# Differenzverst_rker_neu.net
KiCad netlist of a schematic drawn in EAGLE
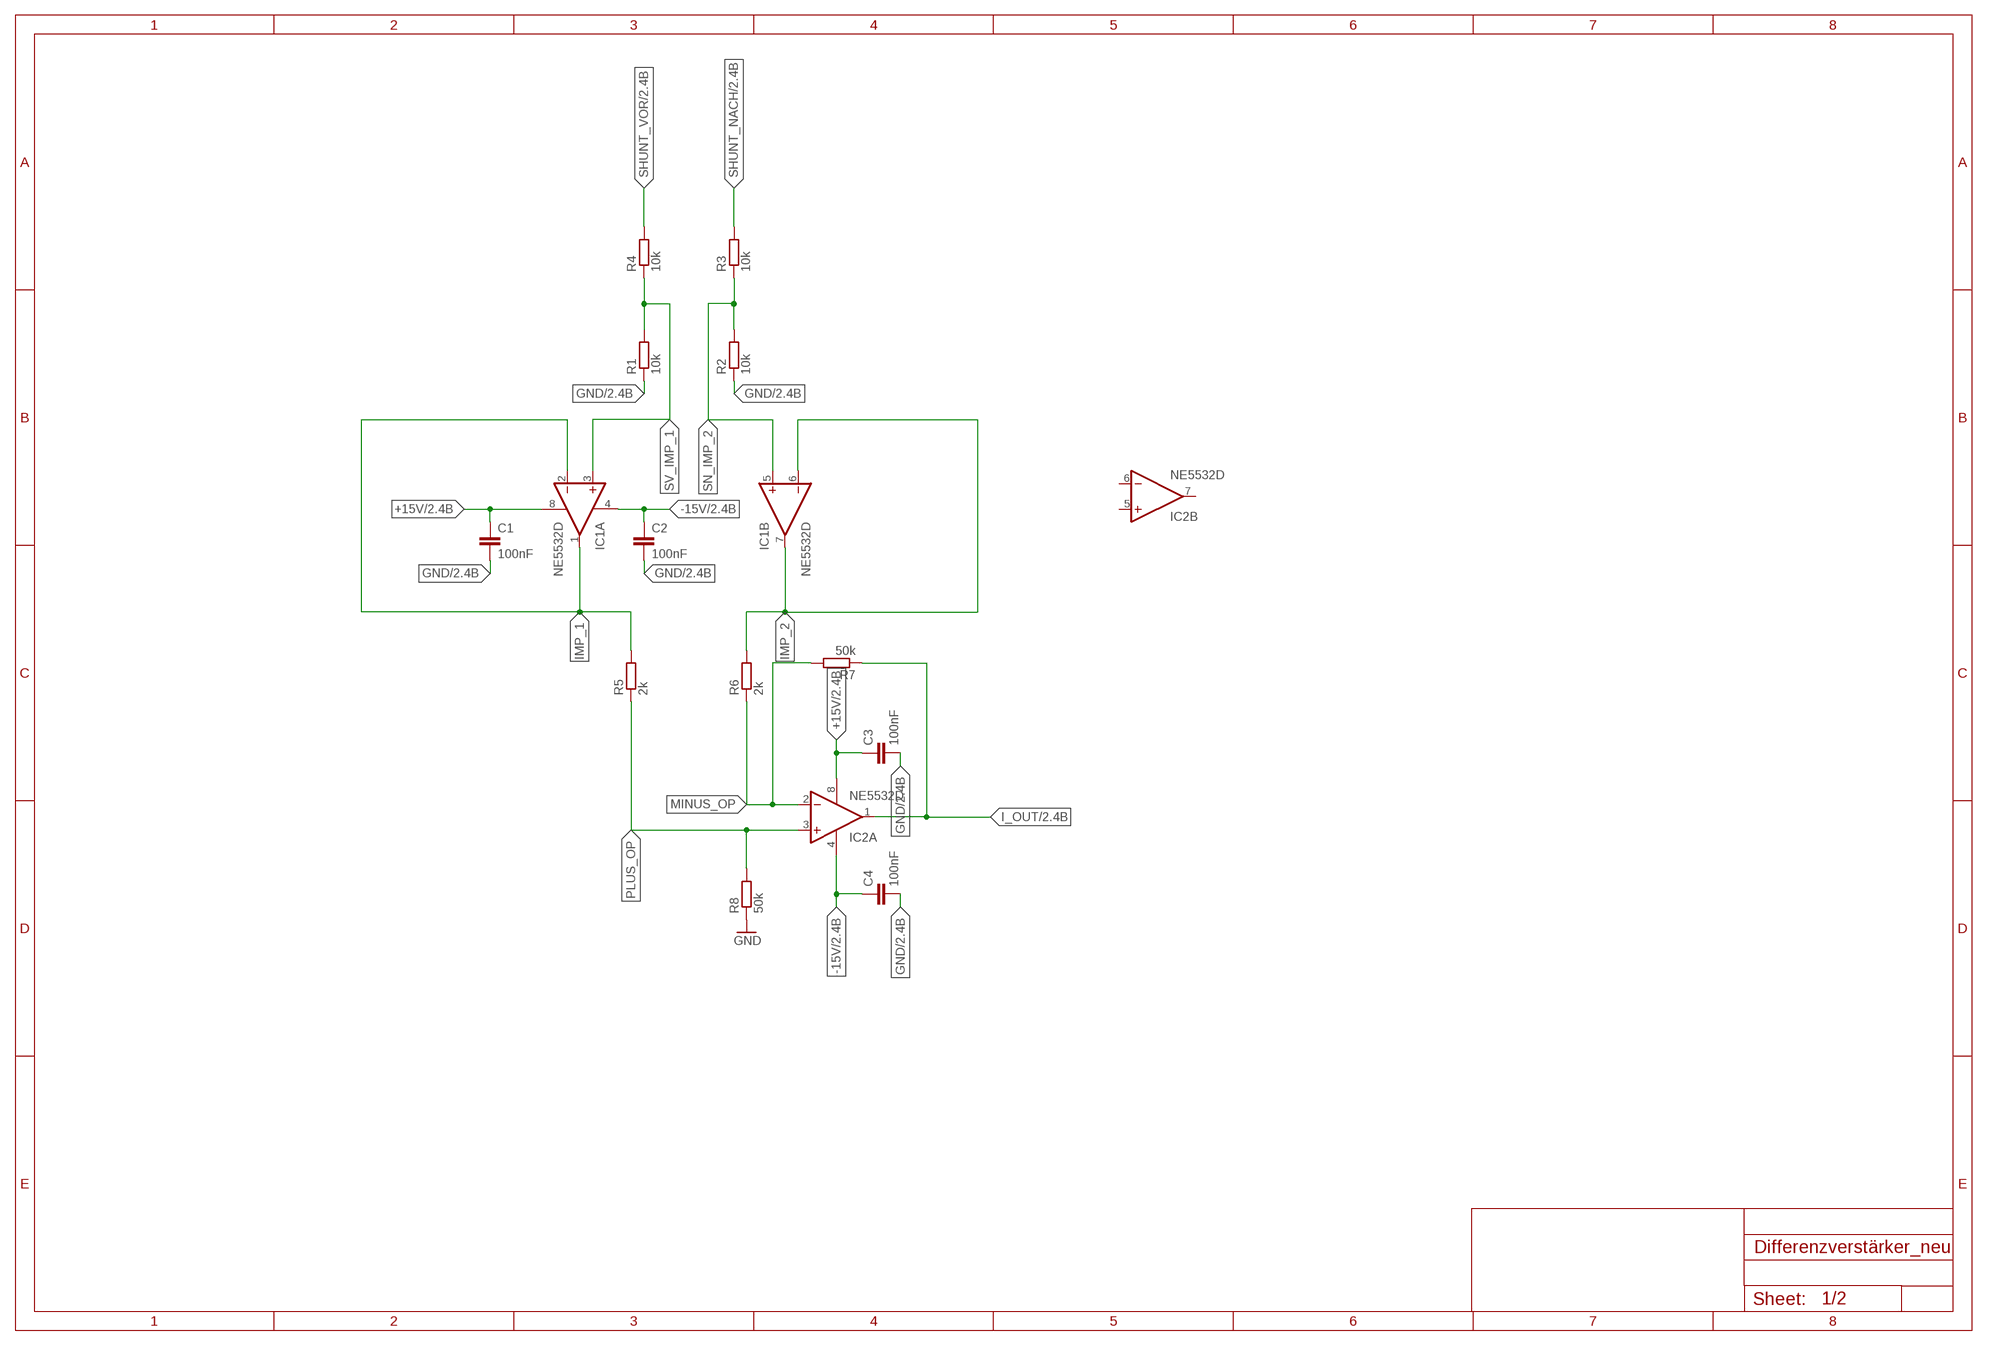
[diagram p0: schematic, sheet 1]
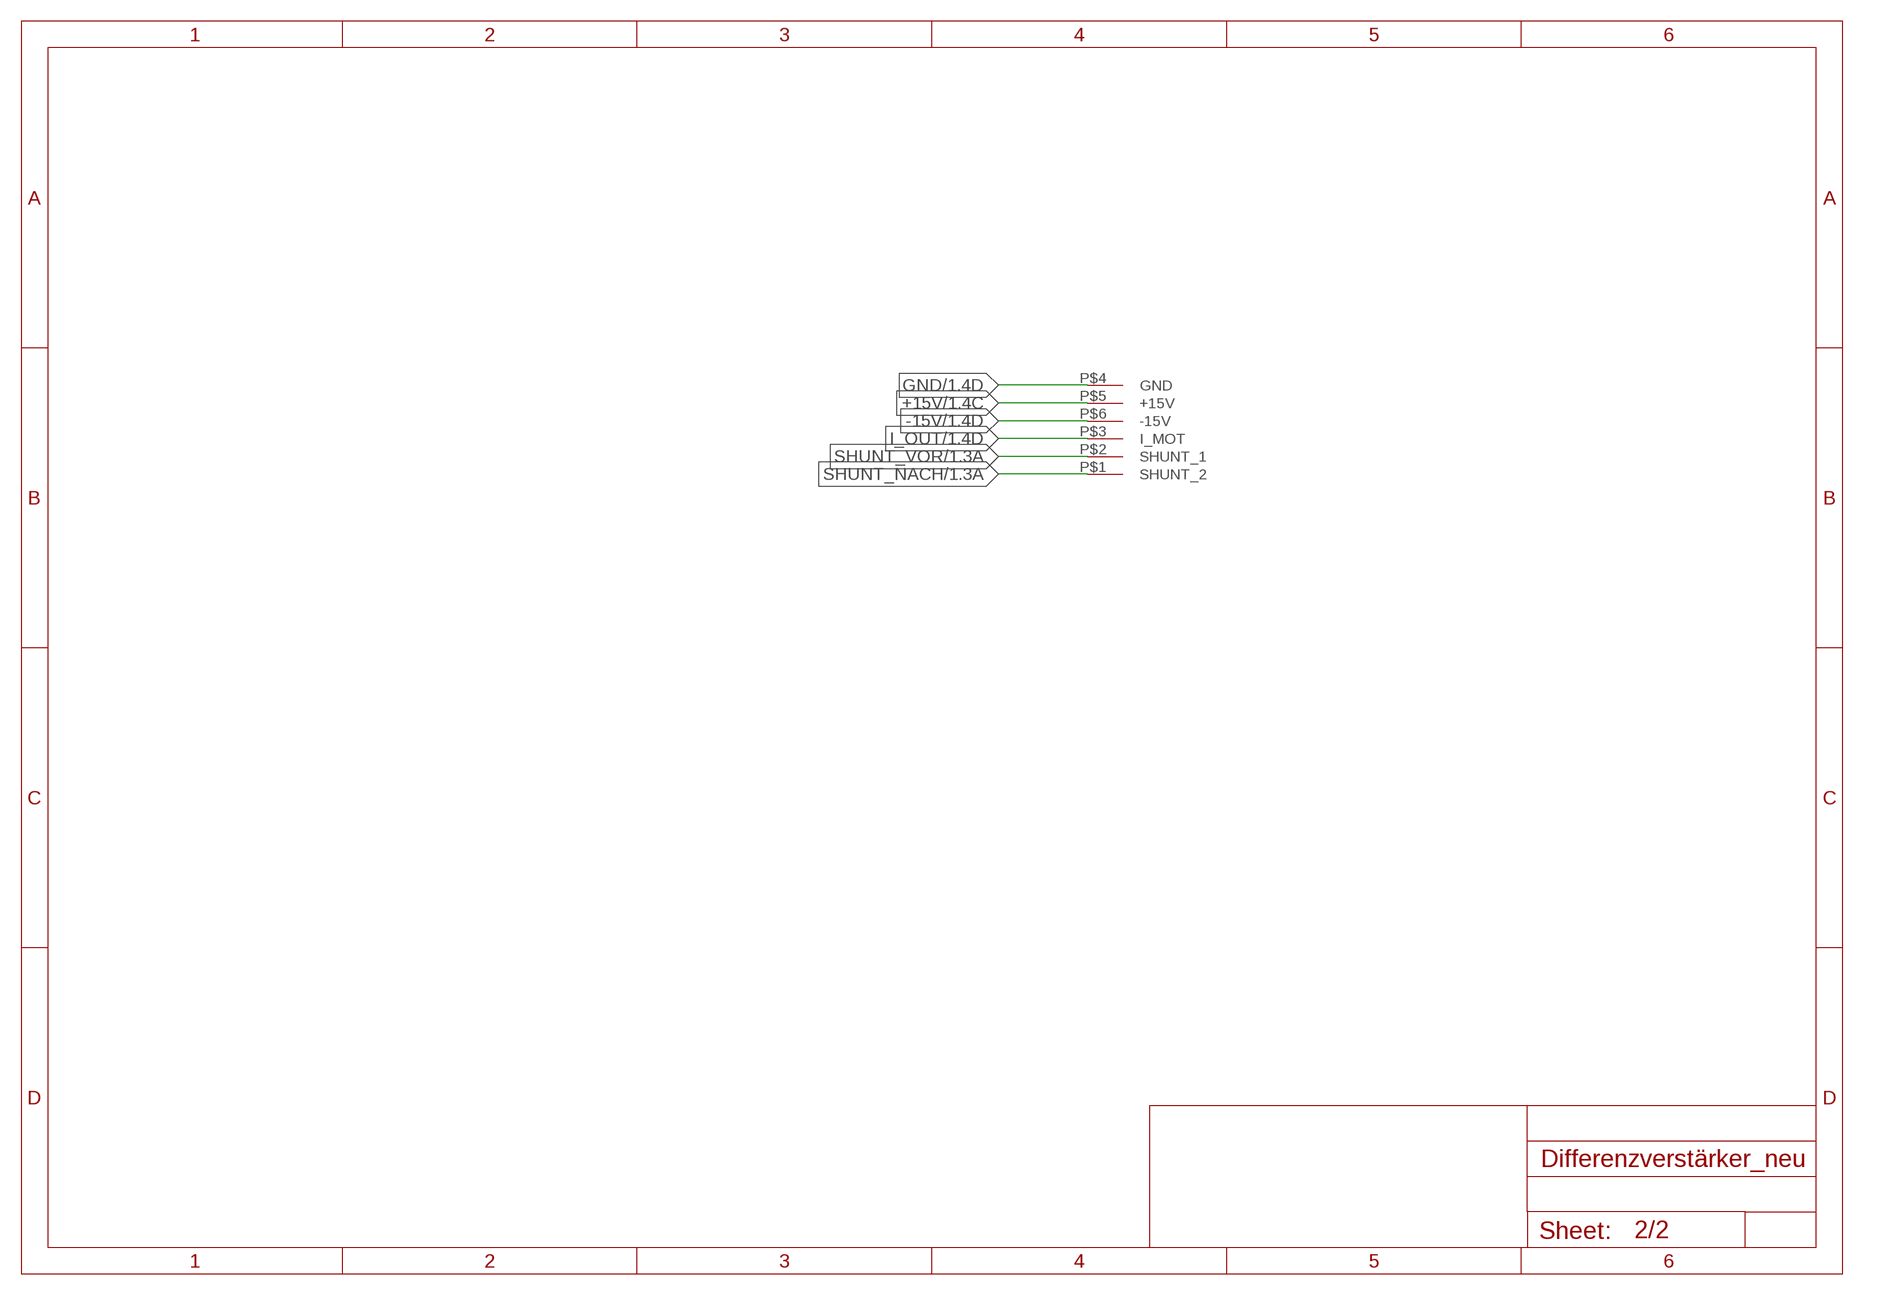
[diagram p1: schematic, sheet 2]

(export (version "E")
  (design (tool "Eeschema 10.0.6"))
  (components
    (comp (ref "U$2")
      (value "ADAPTERPLATINE_OPSHUNT")
      (footprint "eagle-import:ADAPTERPLATINE_OPSHUNT")
      (libsource (lib "eagle-import") (part "ADAPTERPLATINE_OPSHUNT"))
    )
    (comp (ref "C1")
      (value "100nF")
      (footprint "eagle-import:C0805")
      (libsource (lib "eagle-import") (part "C-EUC0805"))
    )
    (comp (ref "C2")
      (value "100nF")
      (footprint "eagle-import:C0805")
      (libsource (lib "eagle-import") (part "C-EUC0805"))
    )
    (comp (ref "C3")
      (value "100nF")
      (footprint "eagle-import:C0805")
      (libsource (lib "eagle-import") (part "C-EUC0805"))
    )
    (comp (ref "C4")
      (value "100nF")
      (footprint "eagle-import:C0805")
      (libsource (lib "eagle-import") (part "C-EUC0805"))
    )
    (comp (ref "IC1")
      (value "NE5532D")
      (footprint "eagle-import:SO08")
      (libsource (lib "eagle-import") (part "NE5532D"))
    )
    (comp (ref "IC2")
      (value "NE5532D")
      (footprint "eagle-import:SO08")
      (libsource (lib "eagle-import") (part "NE5532D"))
    )
    (comp (ref "R1")
      (value "10k")
      (footprint "eagle-import:R0805")
      (libsource (lib "eagle-import") (part "R-EU_R0805"))
    )
    (comp (ref "R2")
      (value "10k")
      (footprint "eagle-import:R0805")
      (libsource (lib "eagle-import") (part "R-EU_R0805"))
    )
    (comp (ref "R3")
      (value "10k")
      (footprint "eagle-import:R0805")
      (libsource (lib "eagle-import") (part "R-EU_R0805"))
    )
    (comp (ref "R4")
      (value "10k")
      (footprint "eagle-import:R0805")
      (libsource (lib "eagle-import") (part "R-EU_R0805"))
    )
    (comp (ref "R5")
      (value "2k")
      (footprint "eagle-import:R0805")
      (libsource (lib "eagle-import") (part "R-EU_R0805"))
    )
    (comp (ref "R6")
      (value "2k")
      (footprint "eagle-import:R0805")
      (libsource (lib "eagle-import") (part "R-EU_R0805"))
    )
    (comp (ref "R7")
      (value "50k")
      (footprint "eagle-import:R0805")
      (libsource (lib "eagle-import") (part "R-EU_R0805"))
    )
    (comp (ref "R8")
      (value "50k")
      (footprint "eagle-import:R0805")
      (libsource (lib "eagle-import") (part "R-EU_R0805"))
    )
  )
  (nets
    (net (code "1") (name "+15V") (class "Default")
      (node (ref "C1") (pin "1") (pinfunction "1_1") (pintype "passive"))
      (node (ref "C3") (pin "1") (pinfunction "1_1") (pintype "passive"))
      (node (ref "IC1") (pin "8") (pinfunction "V+_8") (pintype "power_in"))
      (node (ref "IC2") (pin "8") (pinfunction "V+_8") (pintype "power_in"))
      (node (ref "U$2") (pin "P$5") (pinfunction "+15V_P$5") (pintype "bidirectional"))
    )
    (net (code "2") (name "-15V") (class "Default")
      (node (ref "C2") (pin "1") (pinfunction "1_1") (pintype "passive"))
      (node (ref "C4") (pin "1") (pinfunction "1_1") (pintype "passive"))
      (node (ref "IC1") (pin "4") (pinfunction "V-_4") (pintype "power_in"))
      (node (ref "IC2") (pin "4") (pinfunction "V-_4") (pintype "power_in"))
      (node (ref "U$2") (pin "P$6") (pinfunction "-15V_P$6") (pintype "bidirectional"))
    )
    (net (code "3") (name "GND") (class "Default")
      (node (ref "C1") (pin "2") (pinfunction "2_2") (pintype "passive"))
      (node (ref "C2") (pin "2") (pinfunction "2_2") (pintype "passive"))
      (node (ref "C3") (pin "2") (pinfunction "2_2") (pintype "passive"))
      (node (ref "C4") (pin "2") (pinfunction "2_2") (pintype "passive"))
      (node (ref "R1") (pin "1") (pinfunction "1_1") (pintype "passive"))
      (node (ref "R2") (pin "1") (pinfunction "1_1") (pintype "passive"))
      (node (ref "R8") (pin "1") (pinfunction "1_1") (pintype "passive"))
      (node (ref "U$2") (pin "P$4") (pinfunction "GND_P$4") (pintype "bidirectional"))
    )
    (net (code "4") (name "IMP_1") (class "Default")
      (node (ref "IC1") (pin "1") (pinfunction "OUT_1") (pintype "output"))
      (node (ref "IC1") (pin "2") (pinfunction "-IN_2") (pintype "input"))
      (node (ref "R5") (pin "2") (pinfunction "2_2") (pintype "passive"))
    )
    (net (code "5") (name "IMP_2") (class "Default")
      (node (ref "IC1") (pin "6") (pinfunction "-IN_6") (pintype "input"))
      (node (ref "IC1") (pin "7") (pinfunction "OUT_7") (pintype "output"))
      (node (ref "R6") (pin "2") (pinfunction "2_2") (pintype "passive"))
    )
    (net (code "6") (name "I_OUT") (class "Default")
      (node (ref "IC2") (pin "1") (pinfunction "OUT_1") (pintype "output"))
      (node (ref "R7") (pin "1") (pinfunction "1_1") (pintype "passive"))
      (node (ref "U$2") (pin "P$3") (pinfunction "I_MOT_P$3") (pintype "bidirectional"))
    )
    (net (code "7") (name "MINUS_OP") (class "Default")
      (node (ref "IC2") (pin "2") (pinfunction "-IN_2") (pintype "input"))
      (node (ref "R6") (pin "1") (pinfunction "1_1") (pintype "passive"))
      (node (ref "R7") (pin "2") (pinfunction "2_2") (pintype "passive"))
    )
    (net (code "8") (name "PLUS_OP") (class "Default")
      (node (ref "IC2") (pin "3") (pinfunction "+IN_3") (pintype "input"))
      (node (ref "R5") (pin "1") (pinfunction "1_1") (pintype "passive"))
      (node (ref "R8") (pin "2") (pinfunction "2_2") (pintype "passive"))
    )
    (net (code "9") (name "SHUNT_NACH") (class "Default")
      (node (ref "R3") (pin "2") (pinfunction "2_2") (pintype "passive"))
      (node (ref "U$2") (pin "P$1") (pinfunction "SHUNT_2_P$1") (pintype "bidirectional"))
    )
    (net (code "10") (name "SHUNT_VOR") (class "Default")
      (node (ref "R4") (pin "2") (pinfunction "2_2") (pintype "passive"))
      (node (ref "U$2") (pin "P$2") (pinfunction "SHUNT_1_P$2") (pintype "bidirectional"))
    )
    (net (code "11") (name "SN_IMP_2") (class "Default")
      (node (ref "IC1") (pin "5") (pinfunction "+IN_5") (pintype "input"))
      (node (ref "R2") (pin "2") (pinfunction "2_2") (pintype "passive"))
      (node (ref "R3") (pin "1") (pinfunction "1_1") (pintype "passive"))
    )
    (net (code "12") (name "SV_IMP_1") (class "Default")
      (node (ref "IC1") (pin "3") (pinfunction "+IN_3") (pintype "input"))
      (node (ref "R1") (pin "2") (pinfunction "2_2") (pintype "passive"))
      (node (ref "R4") (pin "1") (pinfunction "1_1") (pintype "passive"))
    )
    (net (code "13") (name "unconnected-(IC2B-+IN-Pad5)") (class "Default")
      (node (ref "IC2") (pin "5") (pinfunction "+IN_5") (pintype "input"))
    )
    (net (code "14") (name "unconnected-(IC2B--IN-Pad6)") (class "Default")
      (node (ref "IC2") (pin "6") (pinfunction "-IN_6") (pintype "input"))
    )
    (net (code "15") (name "unconnected-(IC2B-OUT-Pad7)") (class "Default")
      (node (ref "IC2") (pin "7") (pinfunction "OUT_7") (pintype "output"))
    )
  )
)
